# MotorDriver1.net
KiCad netlist of a schematic drawn in EAGLE
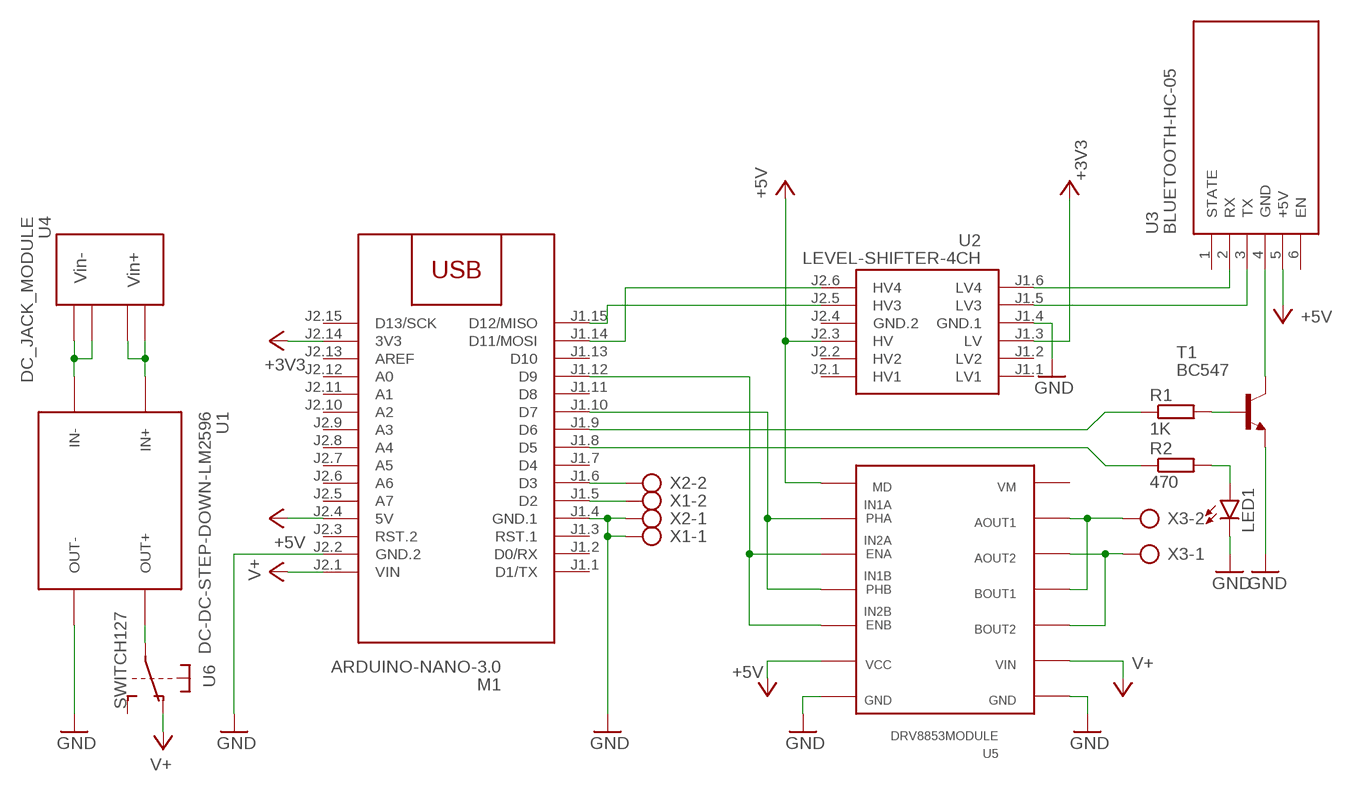
[diagram p0: schematic, sheet 1]

(export (version "E")
  (design (tool "Eeschema 10.0.6"))
  (components
    (comp (ref "LED1")
      (value "LED3MM")
      (footprint "eagle-import:LED3MM")
      (libsource (lib "eagle-import") (part "LED3MM"))
    )
    (comp (ref "M1")
      (value "ARDUINO-NANO-3.0")
      (footprint "eagle-import:ARDUINO-NANO-3.0")
      (libsource (lib "eagle-import") (part "ARDUINO-NANO-3.0"))
    )
    (comp (ref "R1")
      (value "1K")
      (footprint "eagle-import:0207_7")
      (libsource (lib "eagle-import") (part "R-EU_0207/7"))
    )
    (comp (ref "R2")
      (value "470")
      (footprint "eagle-import:0207_7")
      (libsource (lib "eagle-import") (part "R-EU_0207/7"))
    )
    (comp (ref "T1")
      (value "BC547")
      (footprint "eagle-import:TO92")
      (libsource (lib "eagle-import") (part "BC547"))
    )
    (comp (ref "U1")
      (value "DC-DC-STEP-DOWN-LM2596")
      (footprint "eagle-import:DC-DC-STEP-DOWN-LM2596")
      (libsource (lib "eagle-import") (part "DC-DC-STEP-DOWN-LM2596"))
    )
    (comp (ref "U2")
      (value "LEVEL-SHIFTER-4CH")
      (footprint "eagle-import:LEVEL-SHIFTER-4CH")
      (libsource (lib "eagle-import") (part "LEVEL-SHIFTER-4CH"))
    )
    (comp (ref "U3")
      (value "BLUETOOTH-HC-05")
      (footprint "eagle-import:WIRELESS-BLUETOOTH-HC-05")
      (libsource (lib "eagle-import") (part "WIRELESS-BLUETOOTH-HC-05"))
    )
    (comp (ref "U4")
      (value "DC_JACK_MODULE")
      (footprint "eagle-import:MA04-1")
      (libsource (lib "eagle-import") (part "DC_JACK_MODULE"))
    )
    (comp (ref "U5")
      (value "DRV8853MODULE")
      (footprint "eagle-import:DIL14")
      (libsource (lib "eagle-import") (part "DRV8853MODULE"))
    )
    (comp (ref "U6")
      (value "SWITCH127")
      (footprint "eagle-import:SWITCH127")
      (libsource (lib "eagle-import") (part "SWITCH127"))
    )
    (comp (ref "X1")
      (value "AK500/2")
      (footprint "eagle-import:AK500_2")
      (libsource (lib "eagle-import") (part "AK500/2"))
    )
    (comp (ref "X2")
      (value "AK500/2")
      (footprint "eagle-import:AK500_2")
      (libsource (lib "eagle-import") (part "AK500/2"))
    )
    (comp (ref "X3")
      (value "AK500/2")
      (footprint "eagle-import:AK500_2")
      (libsource (lib "eagle-import") (part "AK500/2"))
    )
  )
  (nets
    (net (code "1") (name "+3V3") (class "Default")
      (node (ref "M1") (pin "J2.14") (pinfunction "3V3_J2.14") (pintype "power_in"))
      (node (ref "U2") (pin "J1.3") (pinfunction "LV_J1.3") (pintype "power_in"))
    )
    (net (code "2") (name "+5V") (class "Default")
      (node (ref "M1") (pin "J2.4") (pinfunction "5V_J2.4") (pintype "power_in"))
      (node (ref "U2") (pin "J2.3") (pinfunction "HV_J2.3") (pintype "power_in"))
      (node (ref "U3") (pin "5") (pinfunction "+5V_5") (pintype "power_in"))
      (node (ref "U5") (pin "14") (pinfunction "P$14_14") (pintype "bidirectional"))
      (node (ref "U5") (pin "9") (pinfunction "P$9_9") (pintype "bidirectional"))
    )
    (net (code "3") (name "/GND.2") (class "Default")
      (node (ref "U2") (pin "J2.4") (pinfunction "GND.2_J2.4") (pintype "power_in"))
    )
    (net (code "4") (name "GND") (class "Default")
      (node (ref "LED1") (pin "K") (pinfunction "C_K") (pintype "passive"))
      (node (ref "M1") (pin "J1.4") (pinfunction "GND.1_J1.4") (pintype "power_in"))
      (node (ref "M1") (pin "J2.2") (pinfunction "GND.2_J2.2") (pintype "power_in"))
      (node (ref "T1") (pin "1") (pinfunction "E_1") (pintype "passive"))
      (node (ref "U1") (pin "OUT-") (pinfunction "OUT-_OUT-") (pintype "bidirectional"))
      (node (ref "U2") (pin "J1.4") (pinfunction "GND.1_J1.4") (pintype "power_in"))
      (node (ref "U5") (pin "1") (pinfunction "P$1_1") (pintype "bidirectional"))
      (node (ref "U5") (pin "8") (pinfunction "P$8_8") (pintype "bidirectional"))
      (node (ref "X1") (pin "1") (pinfunction "KL_1") (pintype "passive"))
      (node (ref "X2") (pin "1") (pinfunction "KL_1") (pintype "passive"))
    )
    (net (code "5") (name "Net-(LED1-PadA)") (class "Default")
      (node (ref "LED1") (pin "A") (pinfunction "A_A") (pintype "passive"))
      (node (ref "R2") (pin "2") (pinfunction "2_2") (pintype "passive"))
    )
    (net (code "6") (name "Net-(M1-D2)") (class "Default")
      (node (ref "M1") (pin "J1.5") (pinfunction "D2_J1.5") (pintype "bidirectional"))
      (node (ref "X1") (pin "2") (pinfunction "KL_2") (pintype "passive"))
    )
    (net (code "7") (name "Net-(M1-D3)") (class "Default")
      (node (ref "M1") (pin "J1.6") (pinfunction "D3_J1.6") (pintype "bidirectional"))
      (node (ref "X2") (pin "2") (pinfunction "KL_2") (pintype "passive"))
    )
    (net (code "8") (name "Net-(M1-D5)") (class "Default")
      (node (ref "M1") (pin "J1.8") (pinfunction "D5_J1.8") (pintype "bidirectional"))
      (node (ref "R2") (pin "1") (pinfunction "1_1") (pintype "passive"))
    )
    (net (code "9") (name "Net-(M1-D6)") (class "Default")
      (node (ref "M1") (pin "J1.9") (pinfunction "D6_J1.9") (pintype "bidirectional"))
      (node (ref "R1") (pin "1") (pinfunction "1_1") (pintype "passive"))
    )
    (net (code "10") (name "Net-(M1-D7)") (class "Default")
      (node (ref "M1") (pin "J1.10") (pinfunction "D7_J1.10") (pintype "bidirectional"))
      (node (ref "U5") (pin "11") (pinfunction "P$11_11") (pintype "bidirectional"))
      (node (ref "U5") (pin "13") (pinfunction "P$13_13") (pintype "bidirectional"))
    )
    (net (code "11") (name "Net-(M1-D9)") (class "Default")
      (node (ref "M1") (pin "J1.12") (pinfunction "D9_J1.12") (pintype "bidirectional"))
      (node (ref "U5") (pin "10") (pinfunction "P$10_10") (pintype "bidirectional"))
      (node (ref "U5") (pin "12") (pinfunction "P$12_12") (pintype "bidirectional"))
    )
    (net (code "12") (name "Net-(M1-D11{slash}MOSI)") (class "Default")
      (node (ref "M1") (pin "J1.14") (pinfunction "D11/MOSI_J1.14") (pintype "bidirectional"))
      (node (ref "U2") (pin "J2.6") (pinfunction "HV4_J2.6") (pintype "bidirectional"))
    )
    (net (code "13") (name "Net-(M1-D12{slash}MISO)") (class "Default")
      (node (ref "M1") (pin "J1.15") (pinfunction "D12/MISO_J1.15") (pintype "bidirectional"))
      (node (ref "U2") (pin "J2.5") (pinfunction "HV3_J2.5") (pintype "bidirectional"))
    )
    (net (code "14") (name "Net-(T1-B)") (class "Default")
      (node (ref "R1") (pin "2") (pinfunction "2_2") (pintype "passive"))
      (node (ref "T1") (pin "2") (pinfunction "B_2") (pintype "passive"))
    )
    (net (code "15") (name "Net-(T1-C)") (class "Default")
      (node (ref "T1") (pin "3") (pinfunction "C_3") (pintype "passive"))
      (node (ref "U3") (pin "4") (pinfunction "GND_4") (pintype "power_in"))
    )
    (net (code "16") (name "Net-(U2-LV3)") (class "Default")
      (node (ref "U2") (pin "J1.5") (pinfunction "LV3_J1.5") (pintype "bidirectional"))
      (node (ref "U3") (pin "3") (pinfunction "TX_3") (pintype "bidirectional"))
    )
    (net (code "17") (name "Net-(U2-LV4)") (class "Default")
      (node (ref "U2") (pin "J1.6") (pinfunction "LV4_J1.6") (pintype "bidirectional"))
      (node (ref "U3") (pin "2") (pinfunction "RX_2") (pintype "bidirectional"))
    )
    (net (code "18") (name "Net-(U4-P$1)") (class "Default")
      (node (ref "U1") (pin "IN+") (pinfunction "IN+_IN+") (pintype "bidirectional"))
      (node (ref "U4") (pin "1") (pinfunction "P$1_1") (pintype "bidirectional"))
      (node (ref "U4") (pin "2") (pinfunction "P$2_2") (pintype "bidirectional"))
    )
    (net (code "19") (name "Net-(U4-P$3)") (class "Default")
      (node (ref "U1") (pin "IN-") (pinfunction "IN-_IN-") (pintype "bidirectional"))
      (node (ref "U4") (pin "3") (pinfunction "P$3_3") (pintype "bidirectional"))
      (node (ref "U4") (pin "4") (pinfunction "P$4_4") (pintype "bidirectional"))
    )
    (net (code "20") (name "Net-(U5-P$3)") (class "Default")
      (node (ref "U5") (pin "3") (pinfunction "P$3_3") (pintype "bidirectional"))
      (node (ref "U5") (pin "5") (pinfunction "P$5_5") (pintype "bidirectional"))
      (node (ref "X3") (pin "1") (pinfunction "KL_1") (pintype "passive"))
    )
    (net (code "21") (name "Net-(U5-P$4)") (class "Default")
      (node (ref "U5") (pin "4") (pinfunction "P$4_4") (pintype "bidirectional"))
      (node (ref "U5") (pin "6") (pinfunction "P$6_6") (pintype "bidirectional"))
      (node (ref "X3") (pin "2") (pinfunction "KL_2") (pintype "passive"))
    )
    (net (code "22") (name "Net-(U6-2)") (class "Default")
      (node (ref "U1") (pin "OUT+") (pinfunction "OUT+_OUT+") (pintype "bidirectional"))
      (node (ref "U6") (pin "P$2") (pinfunction "2_P$2") (pintype "passive"))
    )
    (net (code "23") (name "V+") (class "Default")
      (node (ref "M1") (pin "J2.1") (pinfunction "VIN_J2.1") (pintype "power_in"))
      (node (ref "U5") (pin "2") (pinfunction "P$2_2") (pintype "bidirectional"))
      (node (ref "U6") (pin "P$3") (pinfunction "3_P$3") (pintype "passive"))
    )
    (net (code "24") (name "unconnected-(M1-A0-PadJ2.12)") (class "Default")
      (node (ref "M1") (pin "J2.12") (pinfunction "A0_J2.12") (pintype "bidirectional"))
    )
    (net (code "25") (name "unconnected-(M1-A1-PadJ2.11)") (class "Default")
      (node (ref "M1") (pin "J2.11") (pinfunction "A1_J2.11") (pintype "bidirectional"))
    )
    (net (code "26") (name "unconnected-(M1-A2-PadJ2.10)") (class "Default")
      (node (ref "M1") (pin "J2.10") (pinfunction "A2_J2.10") (pintype "bidirectional"))
    )
    (net (code "27") (name "unconnected-(M1-A3-PadJ2.9)") (class "Default")
      (node (ref "M1") (pin "J2.9") (pinfunction "A3_J2.9") (pintype "bidirectional"))
    )
    (net (code "28") (name "unconnected-(M1-A4-PadJ2.8)") (class "Default")
      (node (ref "M1") (pin "J2.8") (pinfunction "A4_J2.8") (pintype "bidirectional"))
    )
    (net (code "29") (name "unconnected-(M1-A5-PadJ2.7)") (class "Default")
      (node (ref "M1") (pin "J2.7") (pinfunction "A5_J2.7") (pintype "bidirectional"))
    )
    (net (code "30") (name "unconnected-(M1-A6-PadJ2.6)") (class "Default")
      (node (ref "M1") (pin "J2.6") (pinfunction "A6_J2.6") (pintype "bidirectional"))
    )
    (net (code "31") (name "unconnected-(M1-A7-PadJ2.5)") (class "Default")
      (node (ref "M1") (pin "J2.5") (pinfunction "A7_J2.5") (pintype "bidirectional"))
    )
    (net (code "32") (name "unconnected-(M1-AREF-PadJ2.13)") (class "Default")
      (node (ref "M1") (pin "J2.13") (pinfunction "AREF_J2.13") (pintype "bidirectional"))
    )
    (net (code "33") (name "unconnected-(M1-D0{slash}RX-PadJ1.2)") (class "Default")
      (node (ref "M1") (pin "J1.2") (pinfunction "D0/RX_J1.2") (pintype "bidirectional"))
    )
    (net (code "34") (name "unconnected-(M1-D1{slash}TX-PadJ1.1)") (class "Default")
      (node (ref "M1") (pin "J1.1") (pinfunction "D1/TX_J1.1") (pintype "bidirectional"))
    )
    (net (code "35") (name "unconnected-(M1-D4-PadJ1.7)") (class "Default")
      (node (ref "M1") (pin "J1.7") (pinfunction "D4_J1.7") (pintype "bidirectional"))
    )
    (net (code "36") (name "unconnected-(M1-D8-PadJ1.11)") (class "Default")
      (node (ref "M1") (pin "J1.11") (pinfunction "D8_J1.11") (pintype "bidirectional"))
    )
    (net (code "37") (name "unconnected-(M1-D10-PadJ1.13)") (class "Default")
      (node (ref "M1") (pin "J1.13") (pinfunction "D10_J1.13") (pintype "bidirectional"))
    )
    (net (code "38") (name "unconnected-(M1-D13{slash}SCK-PadJ2.15)") (class "Default")
      (node (ref "M1") (pin "J2.15") (pinfunction "D13/SCK_J2.15") (pintype "bidirectional"))
    )
    (net (code "39") (name "unconnected-(M1-RST.1-PadJ1.3)") (class "Default")
      (node (ref "M1") (pin "J1.3") (pinfunction "RST.1_J1.3") (pintype "bidirectional"))
    )
    (net (code "40") (name "unconnected-(M1-RST.2-PadJ2.3)") (class "Default")
      (node (ref "M1") (pin "J2.3") (pinfunction "RST.2_J2.3") (pintype "bidirectional"))
    )
    (net (code "41") (name "unconnected-(U2-HV1-PadJ2.1)") (class "Default")
      (node (ref "U2") (pin "J2.1") (pinfunction "HV1_J2.1") (pintype "bidirectional"))
    )
    (net (code "42") (name "unconnected-(U2-HV2-PadJ2.2)") (class "Default")
      (node (ref "U2") (pin "J2.2") (pinfunction "HV2_J2.2") (pintype "bidirectional"))
    )
    (net (code "43") (name "unconnected-(U2-LV1-PadJ1.1)") (class "Default")
      (node (ref "U2") (pin "J1.1") (pinfunction "LV1_J1.1") (pintype "bidirectional"))
    )
    (net (code "44") (name "unconnected-(U2-LV2-PadJ1.2)") (class "Default")
      (node (ref "U2") (pin "J1.2") (pinfunction "LV2_J1.2") (pintype "bidirectional"))
    )
    (net (code "45") (name "unconnected-(U3-EN-Pad6)") (class "Default")
      (node (ref "U3") (pin "6") (pinfunction "EN_6") (pintype "bidirectional"))
    )
    (net (code "46") (name "unconnected-(U3-STATE-Pad1)") (class "Default")
      (node (ref "U3") (pin "1") (pinfunction "STATE_1") (pintype "bidirectional"))
    )
    (net (code "47") (name "unconnected-(U5-P$7-Pad7)") (class "Default")
      (node (ref "U5") (pin "7") (pinfunction "P$7_7") (pintype "bidirectional"))
    )
    (net (code "48") (name "unconnected-(U6-1-PadP$1)") (class "Default")
      (node (ref "U6") (pin "P$1") (pinfunction "1_P$1") (pintype "passive"))
    )
  )
)
